# St_Olavs_Alarm.net
KiCad netlist of a schematic drawn in Altium Designer
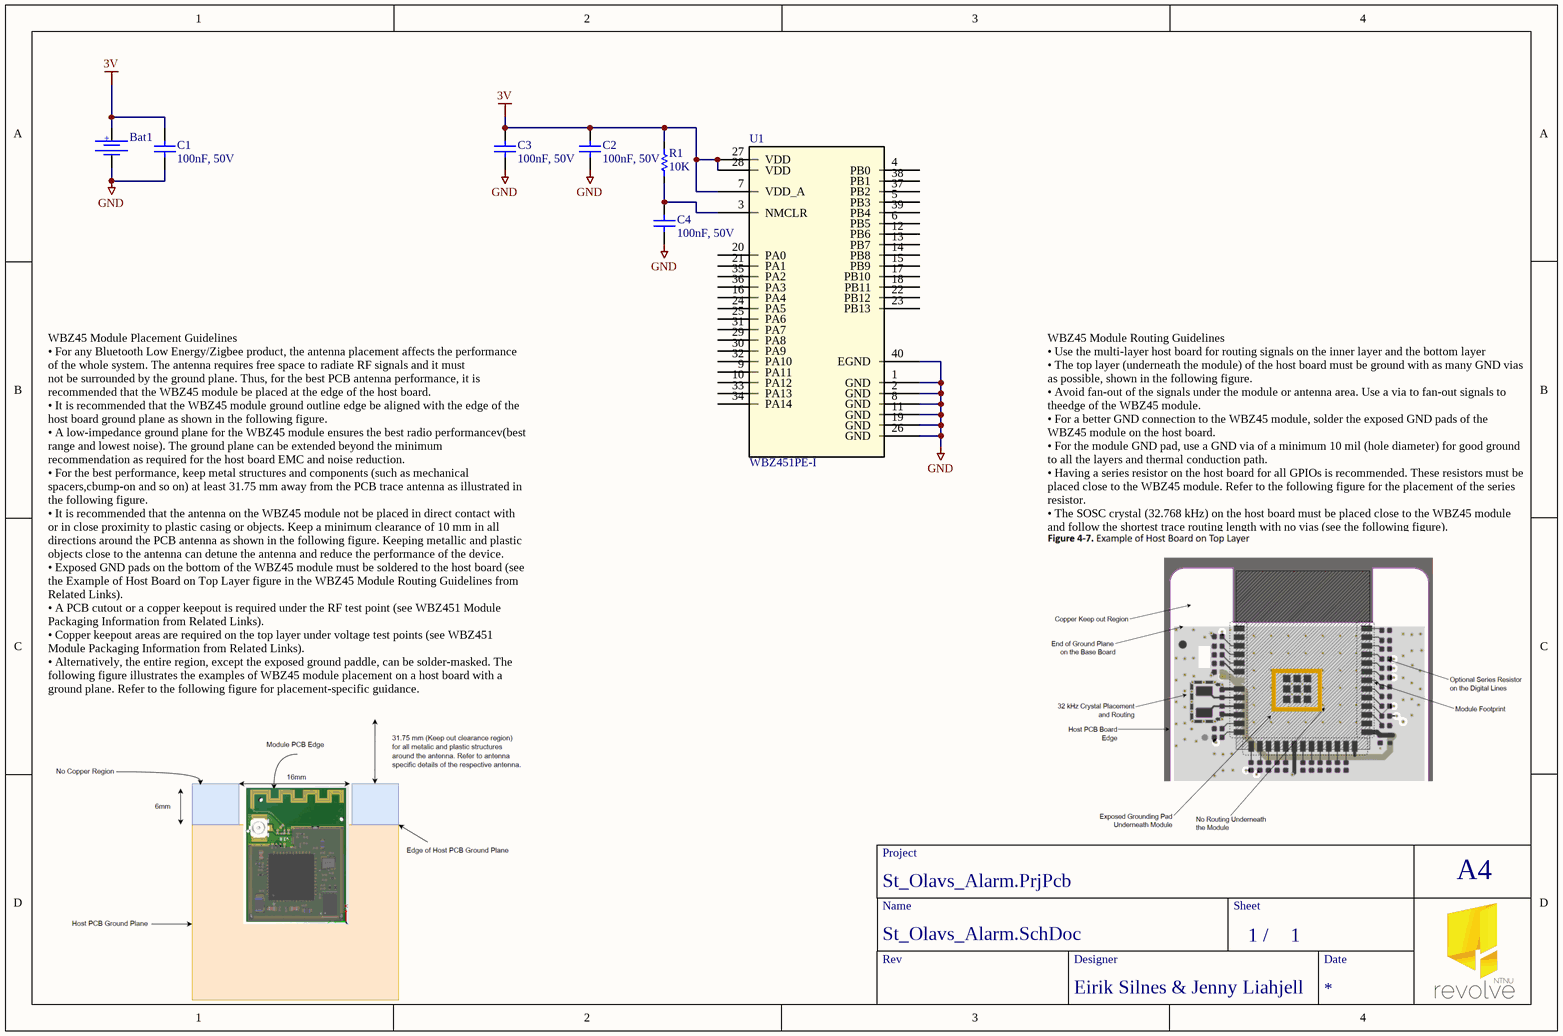
[diagram p0: St_Olavs_Alarm.SchDoc]

(export (version "E")
  (design (tool "Eeschema 10.0.6"))
  (components
    (comp (ref "Bat1")
      (value "Bat Holder L-KLS5-CR2032-23-B1")
      (footprint "L-KLS5-CR2032-23-B1")
      (description "Bat Holder CR2032 SMD")
      (fields
        (field (name "MANUFACTURER") "KLS Electronic")
        (field (name "MANUFACTURER PART NUMBER") "L-KLS5-CR2032-23-B1")
        (field (name "AUTHOR") "rsk")
      )
      (libsource (lib "Revolve NTNU") (part "Bat Holder L-KLS5-CR2032-23-B1"))
    )
    (comp (ref "C1")
      (value "100nF, 50V")
      (footprint "0603 Capacitor")
      (description "100nF, 50V, 10%, X7R, 0603")
      (libsource (lib "Revolve NTNU") (part "CAP"))
    )
    (comp (ref "C2")
      (value "100nF, 50V")
      (footprint "0603 Capacitor")
      (description "100nF, 50V, 10%, X7R, 0603")
      (libsource (lib "Revolve NTNU") (part "CAP"))
    )
    (comp (ref "C3")
      (value "100nF, 50V")
      (footprint "0603 Capacitor")
      (description "100nF, 50V, 10%, X7R, 0603")
      (libsource (lib "Revolve NTNU") (part "CAP"))
    )
    (comp (ref "C4")
      (value "100nF, 50V")
      (footprint "0603 Capacitor")
      (description "100nF, 50V, 10%, X7R, 0603")
      (libsource (lib "Revolve NTNU") (part "CAP"))
    )
    (comp (ref "R1")
      (value "10K")
      (footprint "0603 Resistor")
      (description "10K, 1%, 1/10W, 0603")
      (libsource (lib "Revault") (part "Resistor"))
    )
    (comp (ref "U1")
      (value "WBZ451PE-I")
      (footprint "WBZ451_MCH")
      (description "No Description Available")
      (fields (field (name "COPYRIGHT") "Copyright (C) 2024 Ultra Librarian. All rights reserved."))
      (libsource (lib "Schlib1") (part "WBZ451PE-I"))
    )
  )
  (nets
    (net (code "1") (name "3V") (class "Default")
      (node (ref "Bat1") (pin "1") (pintype "passive"))
      (node (ref "C1") (pin "2") (pinfunction "2_2") (pintype "passive"))
      (node (ref "C2") (pin "2") (pinfunction "2_2") (pintype "passive"))
      (node (ref "C3") (pin "2") (pinfunction "2_2") (pintype "passive"))
      (node (ref "R1") (pin "1") (pinfunction "1_1") (pintype "passive"))
      (node (ref "U1") (pin "27") (pinfunction "VDD_27") (pintype "power_in"))
      (node (ref "U1") (pin "28") (pinfunction "VDD_28") (pintype "power_in"))
      (node (ref "U1") (pin "7") (pinfunction "VDD_A_7") (pintype "power_in"))
    )
    (net (code "2") (name "GND") (class "Default")
      (node (ref "Bat1") (pin "2") (pintype "passive"))
      (node (ref "C1") (pin "1") (pinfunction "1_1") (pintype "passive"))
      (node (ref "C2") (pin "1") (pinfunction "1_1") (pintype "passive"))
      (node (ref "C3") (pin "1") (pinfunction "1_1") (pintype "passive"))
      (node (ref "C4") (pin "1") (pinfunction "1_1") (pintype "passive"))
      (node (ref "U1") (pin "1") (pinfunction "GND_1") (pintype "power_in"))
      (node (ref "U1") (pin "11") (pinfunction "GND_11") (pintype "power_in"))
      (node (ref "U1") (pin "19") (pinfunction "GND_19") (pintype "power_in"))
      (node (ref "U1") (pin "2") (pinfunction "GND_2") (pintype "power_in"))
      (node (ref "U1") (pin "26") (pinfunction "GND_26") (pintype "power_in"))
      (node (ref "U1") (pin "40") (pinfunction "EGND_40") (pintype "power_in"))
      (node (ref "U1") (pin "8") (pinfunction "GND_8") (pintype "power_in"))
    )
    (net (code "3") (name "Net-(U1-NMCLR)") (class "Default")
      (node (ref "C4") (pin "2") (pinfunction "2_2") (pintype "passive"))
      (node (ref "R1") (pin "2") (pinfunction "2_2") (pintype "passive"))
      (node (ref "U1") (pin "3") (pinfunction "NMCLR_3") (pintype "passive"))
    )
    (net (code "4") (name "unconnected-(U1-PA0-Pad20)") (class "Default")
      (node (ref "U1") (pin "20") (pinfunction "PA0_20") (pintype "passive"))
    )
    (net (code "5") (name "unconnected-(U1-PA1-Pad21)") (class "Default")
      (node (ref "U1") (pin "21") (pinfunction "PA1_21") (pintype "passive"))
    )
    (net (code "6") (name "unconnected-(U1-PA2-Pad35)") (class "Default")
      (node (ref "U1") (pin "35") (pinfunction "PA2_35") (pintype "passive"))
    )
    (net (code "7") (name "unconnected-(U1-PA3-Pad36)") (class "Default")
      (node (ref "U1") (pin "36") (pinfunction "PA3_36") (pintype "passive"))
    )
    (net (code "8") (name "unconnected-(U1-PA4-Pad16)") (class "Default")
      (node (ref "U1") (pin "16") (pinfunction "PA4_16") (pintype "passive"))
    )
    (net (code "9") (name "unconnected-(U1-PA5-Pad24)") (class "Default")
      (node (ref "U1") (pin "24") (pinfunction "PA5_24") (pintype "passive"))
    )
    (net (code "10") (name "unconnected-(U1-PA6-Pad25)") (class "Default")
      (node (ref "U1") (pin "25") (pinfunction "PA6_25") (pintype "passive"))
    )
    (net (code "11") (name "unconnected-(U1-PA7-Pad31)") (class "Default")
      (node (ref "U1") (pin "31") (pinfunction "PA7_31") (pintype "passive"))
    )
    (net (code "12") (name "unconnected-(U1-PA8-Pad29)") (class "Default")
      (node (ref "U1") (pin "29") (pinfunction "PA8_29") (pintype "passive"))
    )
    (net (code "13") (name "unconnected-(U1-PA9-Pad30)") (class "Default")
      (node (ref "U1") (pin "30") (pinfunction "PA9_30") (pintype "passive"))
    )
    (net (code "14") (name "unconnected-(U1-PA10-Pad32)") (class "Default")
      (node (ref "U1") (pin "32") (pinfunction "PA10_32") (pintype "passive"))
    )
    (net (code "15") (name "unconnected-(U1-PA11-Pad9)") (class "Default")
      (node (ref "U1") (pin "9") (pinfunction "PA11_9") (pintype "passive"))
    )
    (net (code "16") (name "unconnected-(U1-PA12-Pad10)") (class "Default")
      (node (ref "U1") (pin "10") (pinfunction "PA12_10") (pintype "passive"))
    )
    (net (code "17") (name "unconnected-(U1-PA13-Pad33)") (class "Default")
      (node (ref "U1") (pin "33") (pinfunction "PA13_33") (pintype "passive"))
    )
    (net (code "18") (name "unconnected-(U1-PA14-Pad34)") (class "Default")
      (node (ref "U1") (pin "34") (pinfunction "PA14_34") (pintype "passive"))
    )
    (net (code "19") (name "unconnected-(U1-PB0-Pad4)") (class "Default")
      (node (ref "U1") (pin "4") (pinfunction "PB0_4") (pintype "passive"))
    )
    (net (code "20") (name "unconnected-(U1-PB1-Pad38)") (class "Default")
      (node (ref "U1") (pin "38") (pinfunction "PB1_38") (pintype "passive"))
    )
    (net (code "21") (name "unconnected-(U1-PB2-Pad37)") (class "Default")
      (node (ref "U1") (pin "37") (pinfunction "PB2_37") (pintype "passive"))
    )
    (net (code "22") (name "unconnected-(U1-PB3-Pad5)") (class "Default")
      (node (ref "U1") (pin "5") (pinfunction "PB3_5") (pintype "passive"))
    )
    (net (code "23") (name "unconnected-(U1-PB4-Pad39)") (class "Default")
      (node (ref "U1") (pin "39") (pinfunction "PB4_39") (pintype "passive"))
    )
    (net (code "24") (name "unconnected-(U1-PB5-Pad6)") (class "Default")
      (node (ref "U1") (pin "6") (pinfunction "PB5_6") (pintype "passive"))
    )
    (net (code "25") (name "unconnected-(U1-PB6-Pad12)") (class "Default")
      (node (ref "U1") (pin "12") (pinfunction "PB6_12") (pintype "passive"))
    )
    (net (code "26") (name "unconnected-(U1-PB7-Pad13)") (class "Default")
      (node (ref "U1") (pin "13") (pinfunction "PB7_13") (pintype "passive"))
    )
    (net (code "27") (name "unconnected-(U1-PB8-Pad14)") (class "Default")
      (node (ref "U1") (pin "14") (pinfunction "PB8_14") (pintype "passive"))
    )
    (net (code "28") (name "unconnected-(U1-PB9-Pad15)") (class "Default")
      (node (ref "U1") (pin "15") (pinfunction "PB9_15") (pintype "passive"))
    )
    (net (code "29") (name "unconnected-(U1-PB10-Pad17)") (class "Default")
      (node (ref "U1") (pin "17") (pinfunction "PB10_17") (pintype "passive"))
    )
    (net (code "30") (name "unconnected-(U1-PB11-Pad18)") (class "Default")
      (node (ref "U1") (pin "18") (pinfunction "PB11_18") (pintype "passive"))
    )
    (net (code "31") (name "unconnected-(U1-PB12-Pad22)") (class "Default")
      (node (ref "U1") (pin "22") (pinfunction "PB12_22") (pintype "passive"))
    )
    (net (code "32") (name "unconnected-(U1-PB13-Pad23)") (class "Default")
      (node (ref "U1") (pin "23") (pinfunction "PB13_23") (pintype "passive"))
    )
  )
)
